# Biosensor_v4_3_20141129.net
KiCad netlist of a schematic drawn in EAGLE
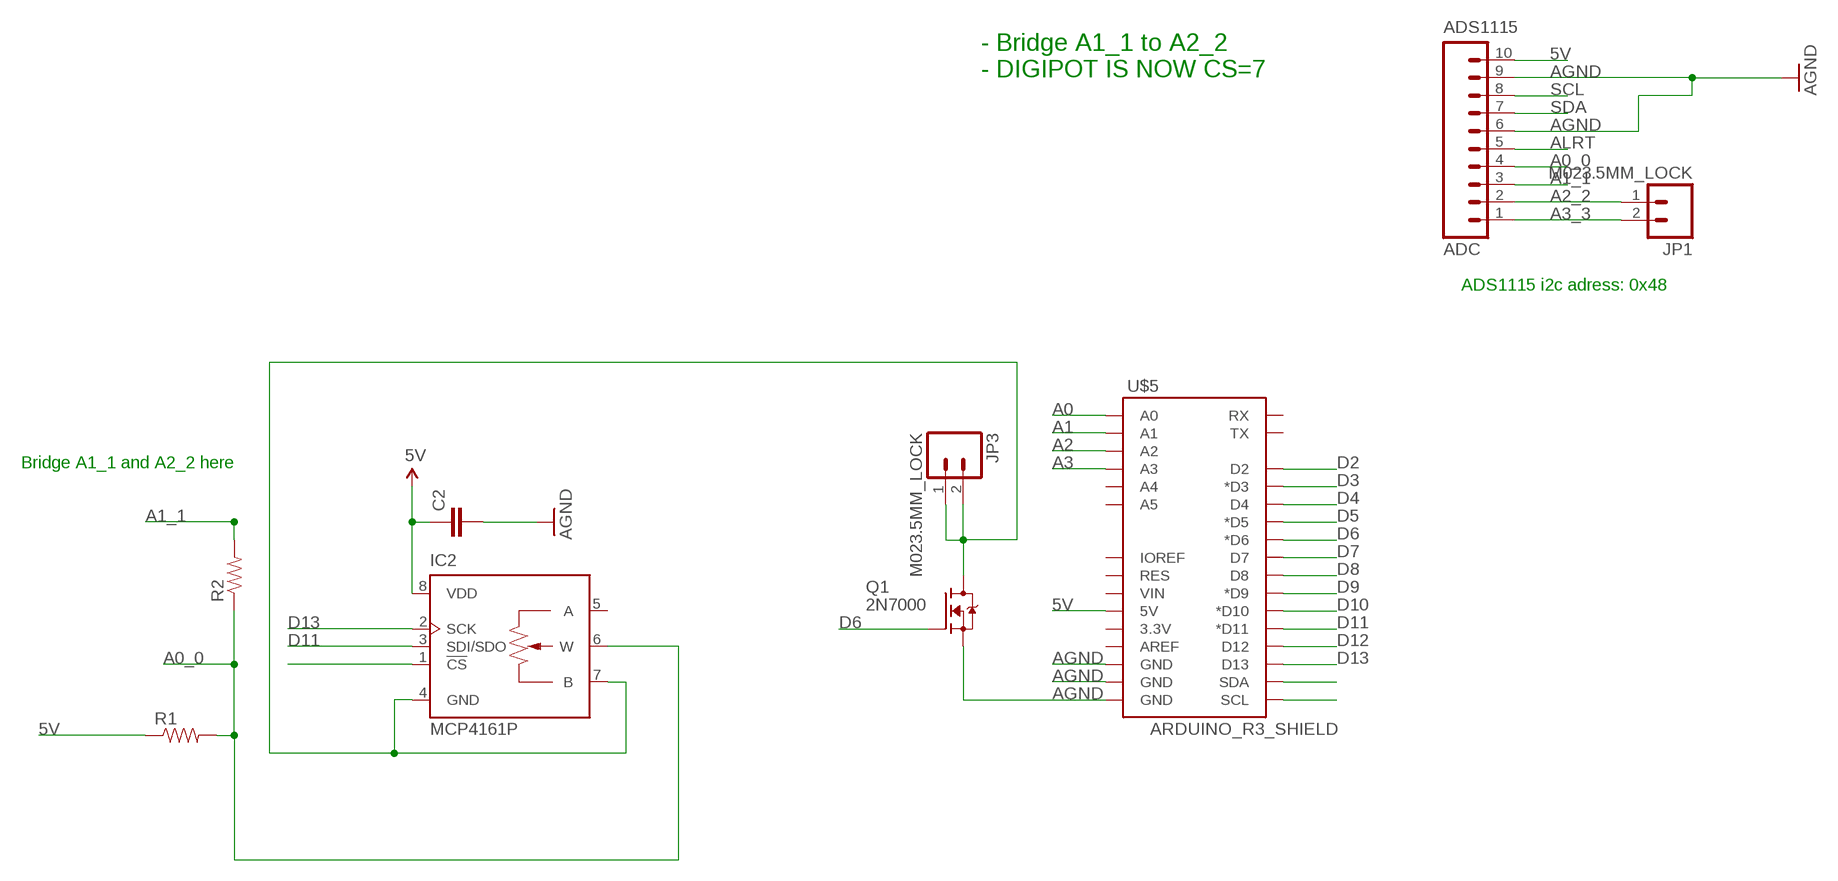
[diagram p0: schematic, sheet 1]

(export (version "E")
  (design (tool "Eeschema 10.0.6"))
  (components
    (comp (ref "ADS1115")
      (value "ADC")
      (footprint "eagle-import:1X10_LOCK")
      (libsource (lib "eagle-import") (part "M10LOCK"))
    )
    (comp (ref "C2")
      (value "CAPKIT")
      (footprint "eagle-import:CAP-PTH-SMALL-KIT")
      (libsource (lib "eagle-import") (part "CAPKIT"))
    )
    (comp (ref "IC2")
      (value "MCP4161P")
      (footprint "eagle-import:DIL08")
      (libsource (lib "eagle-import") (part "MCP4161P"))
    )
    (comp (ref "JP1")
      (value "M023.5MM_LOCK")
      (footprint "eagle-import:SCREWTERMINAL-3.5MM-2_LOCK")
      (libsource (lib "eagle-import") (part "M023.5MM_LOCK"))
    )
    (comp (ref "JP3")
      (value "M023.5MM_LOCK")
      (footprint "eagle-import:SCREWTERMINAL-3.5MM-2_LOCK")
      (libsource (lib "eagle-import") (part "M023.5MM_LOCK"))
    )
    (comp (ref "Q1")
      (value "2N7000")
      (footprint "eagle-import:TO-92")
      (libsource (lib "eagle-import") (part "2N7000"))
    )
    (comp (ref "R1")
      (value "RESISTORPTH-1/2W")
      (footprint "eagle-import:AXIAL-0.5")
      (libsource (lib "eagle-import") (part "RESISTORPTH-1/2W"))
    )
    (comp (ref "R2")
      (value "RESISTORPTH-1/2W")
      (footprint "eagle-import:AXIAL-0.5")
      (libsource (lib "eagle-import") (part "RESISTORPTH-1/2W"))
    )
    (comp (ref "U$5")
      (value "ARDUINO_R3_SHIELD")
      (footprint "eagle-import:UNO_R3_SHIELD")
      (libsource (lib "eagle-import") (part "ARDUINO_R3_SHIELD"))
    )
  )
  (nets
    (net (code "1") (name "/A0") (class "Default")
      (node (ref "U$5") (pin "A0") (pinfunction "A0_A0") (pintype "bidirectional"))
    )
    (net (code "2") (name "/A0_0") (class "Default")
      (node (ref "ADS1115") (pin "4") (pinfunction "4_4") (pintype "passive"))
      (node (ref "IC2") (pin "6") (pinfunction "W_6") (pintype "passive"))
      (node (ref "R1") (pin "P$2") (pinfunction "2_P$2") (pintype "passive"))
      (node (ref "R2") (pin "P$1") (pinfunction "1_P$1") (pintype "passive"))
    )
    (net (code "3") (name "/A1") (class "Default")
      (node (ref "U$5") (pin "A1") (pinfunction "A1_A1") (pintype "bidirectional"))
    )
    (net (code "4") (name "/A1_1") (class "Default")
      (node (ref "ADS1115") (pin "3") (pinfunction "3_3") (pintype "passive"))
      (node (ref "R2") (pin "P$2") (pinfunction "2_P$2") (pintype "passive"))
    )
    (net (code "5") (name "/A2") (class "Default")
      (node (ref "U$5") (pin "A2") (pinfunction "A2_A2") (pintype "bidirectional"))
    )
    (net (code "6") (name "/A2_2") (class "Default")
      (node (ref "ADS1115") (pin "2") (pinfunction "2_2") (pintype "passive"))
      (node (ref "JP1") (pin "1") (pinfunction "1_1") (pintype "passive"))
    )
    (net (code "7") (name "/A3") (class "Default")
      (node (ref "U$5") (pin "A3") (pinfunction "A3_A3") (pintype "bidirectional"))
    )
    (net (code "8") (name "/A3_3") (class "Default")
      (node (ref "ADS1115") (pin "1") (pinfunction "1_1") (pintype "passive"))
      (node (ref "JP1") (pin "2") (pinfunction "2_2") (pintype "passive"))
    )
    (net (code "9") (name "/ALRT") (class "Default")
      (node (ref "ADS1115") (pin "5") (pinfunction "5_5") (pintype "passive"))
    )
    (net (code "10") (name "/D2") (class "Default")
      (node (ref "U$5") (pin "D2") (pinfunction "D2_D2") (pintype "bidirectional"))
    )
    (net (code "11") (name "/D3") (class "Default")
      (node (ref "U$5") (pin "D3") (pinfunction "*D3_D3") (pintype "bidirectional"))
    )
    (net (code "12") (name "/D4") (class "Default")
      (node (ref "U$5") (pin "D4") (pinfunction "D4_D4") (pintype "bidirectional"))
    )
    (net (code "13") (name "/D5") (class "Default")
      (node (ref "U$5") (pin "D5") (pinfunction "*D5_D5") (pintype "bidirectional"))
    )
    (net (code "14") (name "/D6") (class "Default")
      (node (ref "Q1") (pin "2") (pinfunction "G_2") (pintype "passive"))
      (node (ref "U$5") (pin "D6") (pinfunction "*D6_D6") (pintype "bidirectional"))
    )
    (net (code "15") (name "/D7") (class "Default")
      (node (ref "IC2") (pin "1") (pinfunction "~{CS}_1") (pintype "input"))
      (node (ref "U$5") (pin "D7") (pinfunction "D7_D7") (pintype "bidirectional"))
    )
    (net (code "16") (name "/D8") (class "Default")
      (node (ref "U$5") (pin "D8") (pinfunction "D8_D8") (pintype "bidirectional"))
    )
    (net (code "17") (name "/D9") (class "Default")
      (node (ref "U$5") (pin "D9") (pinfunction "*D9_D9") (pintype "bidirectional"))
    )
    (net (code "18") (name "/D10") (class "Default")
      (node (ref "U$5") (pin "D10") (pinfunction "*D10_D10") (pintype "bidirectional"))
    )
    (net (code "19") (name "/D11") (class "Default")
      (node (ref "IC2") (pin "3") (pinfunction "SDI/SDO_3") (pintype "bidirectional"))
      (node (ref "U$5") (pin "D11") (pinfunction "*D11_D11") (pintype "bidirectional"))
    )
    (net (code "20") (name "/D12") (class "Default")
      (node (ref "U$5") (pin "D12") (pinfunction "D12_D12") (pintype "bidirectional"))
    )
    (net (code "21") (name "/D13") (class "Default")
      (node (ref "IC2") (pin "2") (pinfunction "SCK_2") (pintype "input"))
      (node (ref "U$5") (pin "D13") (pinfunction "D13_D13") (pintype "bidirectional"))
    )
    (net (code "22") (name "/SCL") (class "Default")
      (node (ref "ADS1115") (pin "8") (pinfunction "8_8") (pintype "passive"))
      (node (ref "U$5") (pin "SCL") (pinfunction "SCL_SCL") (pintype "bidirectional"))
    )
    (net (code "23") (name "/SDA") (class "Default")
      (node (ref "ADS1115") (pin "7") (pinfunction "7_7") (pintype "passive"))
      (node (ref "U$5") (pin "SDA") (pinfunction "SDA_SDA") (pintype "bidirectional"))
    )
    (net (code "24") (name "5V") (class "Default")
      (node (ref "ADS1115") (pin "10") (pinfunction "10_10") (pintype "passive"))
      (node (ref "C2") (pin "1") (pinfunction "1_1") (pintype "passive"))
      (node (ref "IC2") (pin "8") (pinfunction "VDD_8") (pintype "power_in"))
      (node (ref "R1") (pin "P$1") (pinfunction "1_P$1") (pintype "passive"))
      (node (ref "U$5") (pin "5V") (pinfunction "5V_5V") (pintype "bidirectional"))
    )
    (net (code "25") (name "AGND") (class "Default")
      (node (ref "ADS1115") (pin "6") (pinfunction "6_6") (pintype "passive"))
      (node (ref "ADS1115") (pin "9") (pinfunction "9_9") (pintype "passive"))
      (node (ref "C2") (pin "2") (pinfunction "2_2") (pintype "passive"))
      (node (ref "Q1") (pin "1") (pinfunction "S_1") (pintype "passive"))
      (node (ref "U$5") (pin "GND@0") (pinfunction "GND_GND@0") (pintype "bidirectional"))
      (node (ref "U$5") (pin "GND@1") (pinfunction "GND_GND@1") (pintype "bidirectional"))
      (node (ref "U$5") (pin "GND@2") (pinfunction "GND_GND@2") (pintype "bidirectional"))
    )
    (net (code "26") (name "Net-(IC2-B)") (class "Default")
      (node (ref "IC2") (pin "4") (pinfunction "GND_4") (pintype "power_in"))
      (node (ref "IC2") (pin "7") (pinfunction "B_7") (pintype "passive"))
      (node (ref "JP3") (pin "1") (pinfunction "1_1") (pintype "passive"))
      (node (ref "JP3") (pin "2") (pinfunction "2_2") (pintype "passive"))
      (node (ref "Q1") (pin "3") (pinfunction "D_3") (pintype "passive"))
    )
    (net (code "27") (name "unconnected-(IC2-A-Pad5)") (class "Default")
      (node (ref "IC2") (pin "5") (pinfunction "A_5") (pintype "passive"))
    )
    (net (code "28") (name "unconnected-(U$5-Pad3.3V)") (class "Default")
      (node (ref "U$5") (pin "3.3V") (pinfunction "3.3V_3.3V") (pintype "bidirectional"))
    )
    (net (code "29") (name "unconnected-(U$5-PadA4)") (class "Default")
      (node (ref "U$5") (pin "A4") (pinfunction "A4_A4") (pintype "bidirectional"))
    )
    (net (code "30") (name "unconnected-(U$5-PadA5)") (class "Default")
      (node (ref "U$5") (pin "A5") (pinfunction "A5_A5") (pintype "bidirectional"))
    )
    (net (code "31") (name "unconnected-(U$5-PadAREF)") (class "Default")
      (node (ref "U$5") (pin "AREF") (pinfunction "AREF_AREF") (pintype "bidirectional"))
    )
    (net (code "32") (name "unconnected-(U$5-PadIOREF)") (class "Default")
      (node (ref "U$5") (pin "IOREF") (pinfunction "IOREF_IOREF") (pintype "bidirectional"))
    )
    (net (code "33") (name "unconnected-(U$5-PadRES)") (class "Default")
      (node (ref "U$5") (pin "RES") (pinfunction "RES_RES") (pintype "bidirectional"))
    )
    (net (code "34") (name "unconnected-(U$5-PadRX)") (class "Default")
      (node (ref "U$5") (pin "RX") (pinfunction "RX_RX") (pintype "bidirectional"))
    )
    (net (code "35") (name "unconnected-(U$5-PadTX)") (class "Default")
      (node (ref "U$5") (pin "TX") (pinfunction "TX_TX") (pintype "bidirectional"))
    )
    (net (code "36") (name "unconnected-(U$5-PadVIN)") (class "Default")
      (node (ref "U$5") (pin "VIN") (pinfunction "VIN_VIN") (pintype "bidirectional"))
    )
  )
)
